# 06_-_Multiplexer.net
KiCad netlist of a schematic drawn in Altium Designer
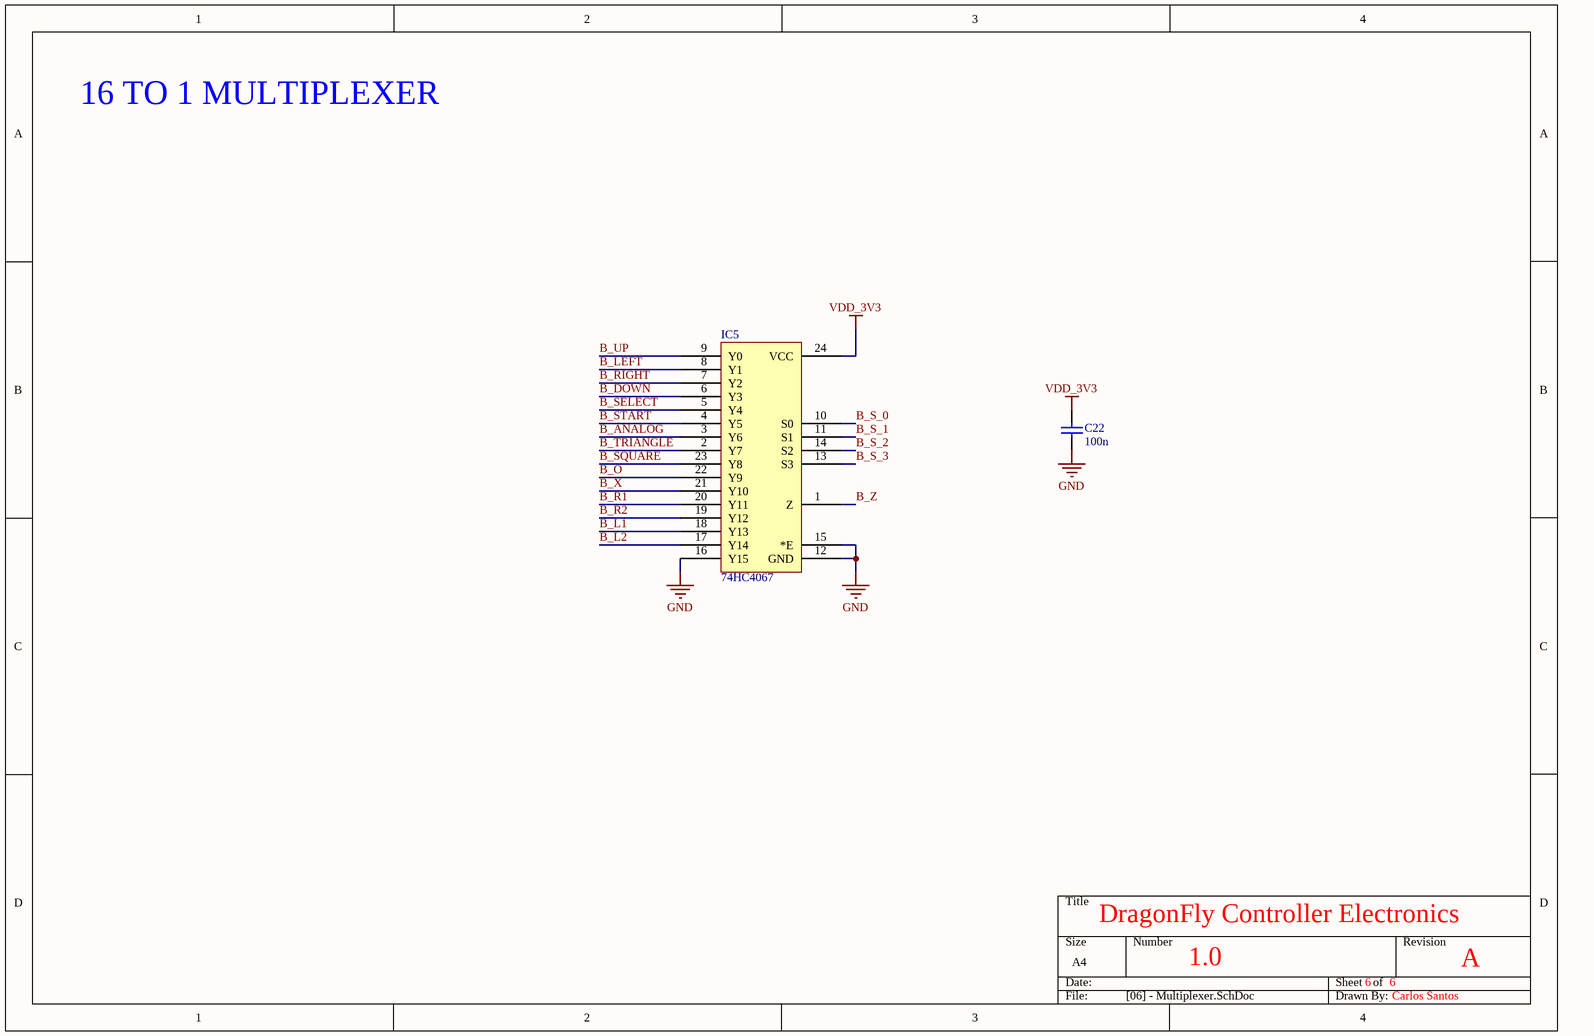
[diagram p0: [06] - Multiplexer.SchDoc]

(export (version "E")
  (design (tool "Eeschema 10.0.6"))
  (components
    (comp (ref "C22")
      (value "100n")
      (footprint "0402 - Capacitor")
      (fields (field (name "Comment") "Capacitor"))
      (libsource (lib "Mine") (part "Capacitor"))
    )
    (comp (ref "IC5")
      (value "74HC4067")
      (footprint "74HC4067-QFN50P350X550X100_HS-25N")
      (fields (field (name "DIGIKEY PART #") "1727-6606-1-ND"))
      (libsource (lib "Mine") (part "74HC4067"))
    )
  )
  (nets
    (net (code "1") (name "/B_ANALOG") (class "Default")
      (node (ref "IC5") (pin "3") (pinfunction "Y6_3") (pintype "passive"))
    )
    (net (code "2") (name "/B_DOWN") (class "Default")
      (node (ref "IC5") (pin "6") (pinfunction "Y3_6") (pintype "passive"))
    )
    (net (code "3") (name "/B_L1") (class "Default")
      (node (ref "IC5") (pin "18") (pinfunction "Y13_18") (pintype "passive"))
    )
    (net (code "4") (name "/B_L2") (class "Default")
      (node (ref "IC5") (pin "17") (pinfunction "Y14_17") (pintype "passive"))
    )
    (net (code "5") (name "/B_LEFT") (class "Default")
      (node (ref "IC5") (pin "8") (pinfunction "Y1_8") (pintype "passive"))
    )
    (net (code "6") (name "/B_O") (class "Default")
      (node (ref "IC5") (pin "22") (pinfunction "Y9_22") (pintype "passive"))
    )
    (net (code "7") (name "/B_R1") (class "Default")
      (node (ref "IC5") (pin "20") (pinfunction "Y11_20") (pintype "passive"))
    )
    (net (code "8") (name "/B_R2") (class "Default")
      (node (ref "IC5") (pin "19") (pinfunction "Y12_19") (pintype "passive"))
    )
    (net (code "9") (name "/B_RIGHT") (class "Default")
      (node (ref "IC5") (pin "7") (pinfunction "Y2_7") (pintype "passive"))
    )
    (net (code "10") (name "/B_SELECT") (class "Default")
      (node (ref "IC5") (pin "5") (pinfunction "Y4_5") (pintype "passive"))
    )
    (net (code "11") (name "/B_SQUARE") (class "Default")
      (node (ref "IC5") (pin "23") (pinfunction "Y8_23") (pintype "passive"))
    )
    (net (code "12") (name "/B_START") (class "Default")
      (node (ref "IC5") (pin "4") (pinfunction "Y5_4") (pintype "passive"))
    )
    (net (code "13") (name "/B_S_0") (class "Default")
      (node (ref "IC5") (pin "10") (pinfunction "S0_10") (pintype "passive"))
    )
    (net (code "14") (name "/B_S_1") (class "Default")
      (node (ref "IC5") (pin "11") (pinfunction "S1_11") (pintype "passive"))
    )
    (net (code "15") (name "/B_S_2") (class "Default")
      (node (ref "IC5") (pin "14") (pinfunction "S2_14") (pintype "passive"))
    )
    (net (code "16") (name "/B_S_3") (class "Default")
      (node (ref "IC5") (pin "13") (pinfunction "S3_13") (pintype "passive"))
    )
    (net (code "17") (name "/B_TRIANGLE") (class "Default")
      (node (ref "IC5") (pin "2") (pinfunction "Y7_2") (pintype "passive"))
    )
    (net (code "18") (name "/B_UP") (class "Default")
      (node (ref "IC5") (pin "9") (pinfunction "Y0_9") (pintype "passive"))
    )
    (net (code "19") (name "/B_X") (class "Default")
      (node (ref "IC5") (pin "21") (pinfunction "Y10_21") (pintype "passive"))
    )
    (net (code "20") (name "/B_Z") (class "Default")
      (node (ref "IC5") (pin "1") (pinfunction "Z_1") (pintype "passive"))
    )
    (net (code "21") (name "GND") (class "Default")
      (node (ref "C22") (pin "1") (pinfunction "1_1") (pintype "passive"))
      (node (ref "IC5") (pin "12") (pinfunction "GND_12") (pintype "passive"))
      (node (ref "IC5") (pin "15") (pinfunction "*E_15") (pintype "passive"))
      (node (ref "IC5") (pin "16") (pinfunction "Y15_16") (pintype "passive"))
    )
    (net (code "22") (name "VDD_3V3") (class "Default")
      (node (ref "C22") (pin "2") (pinfunction "2_2") (pintype "passive"))
      (node (ref "IC5") (pin "24") (pinfunction "VCC_24") (pintype "passive"))
    )
  )
)
